# CeeGrid_Anschluss.net
KiCad netlist of a schematic drawn in EAGLE
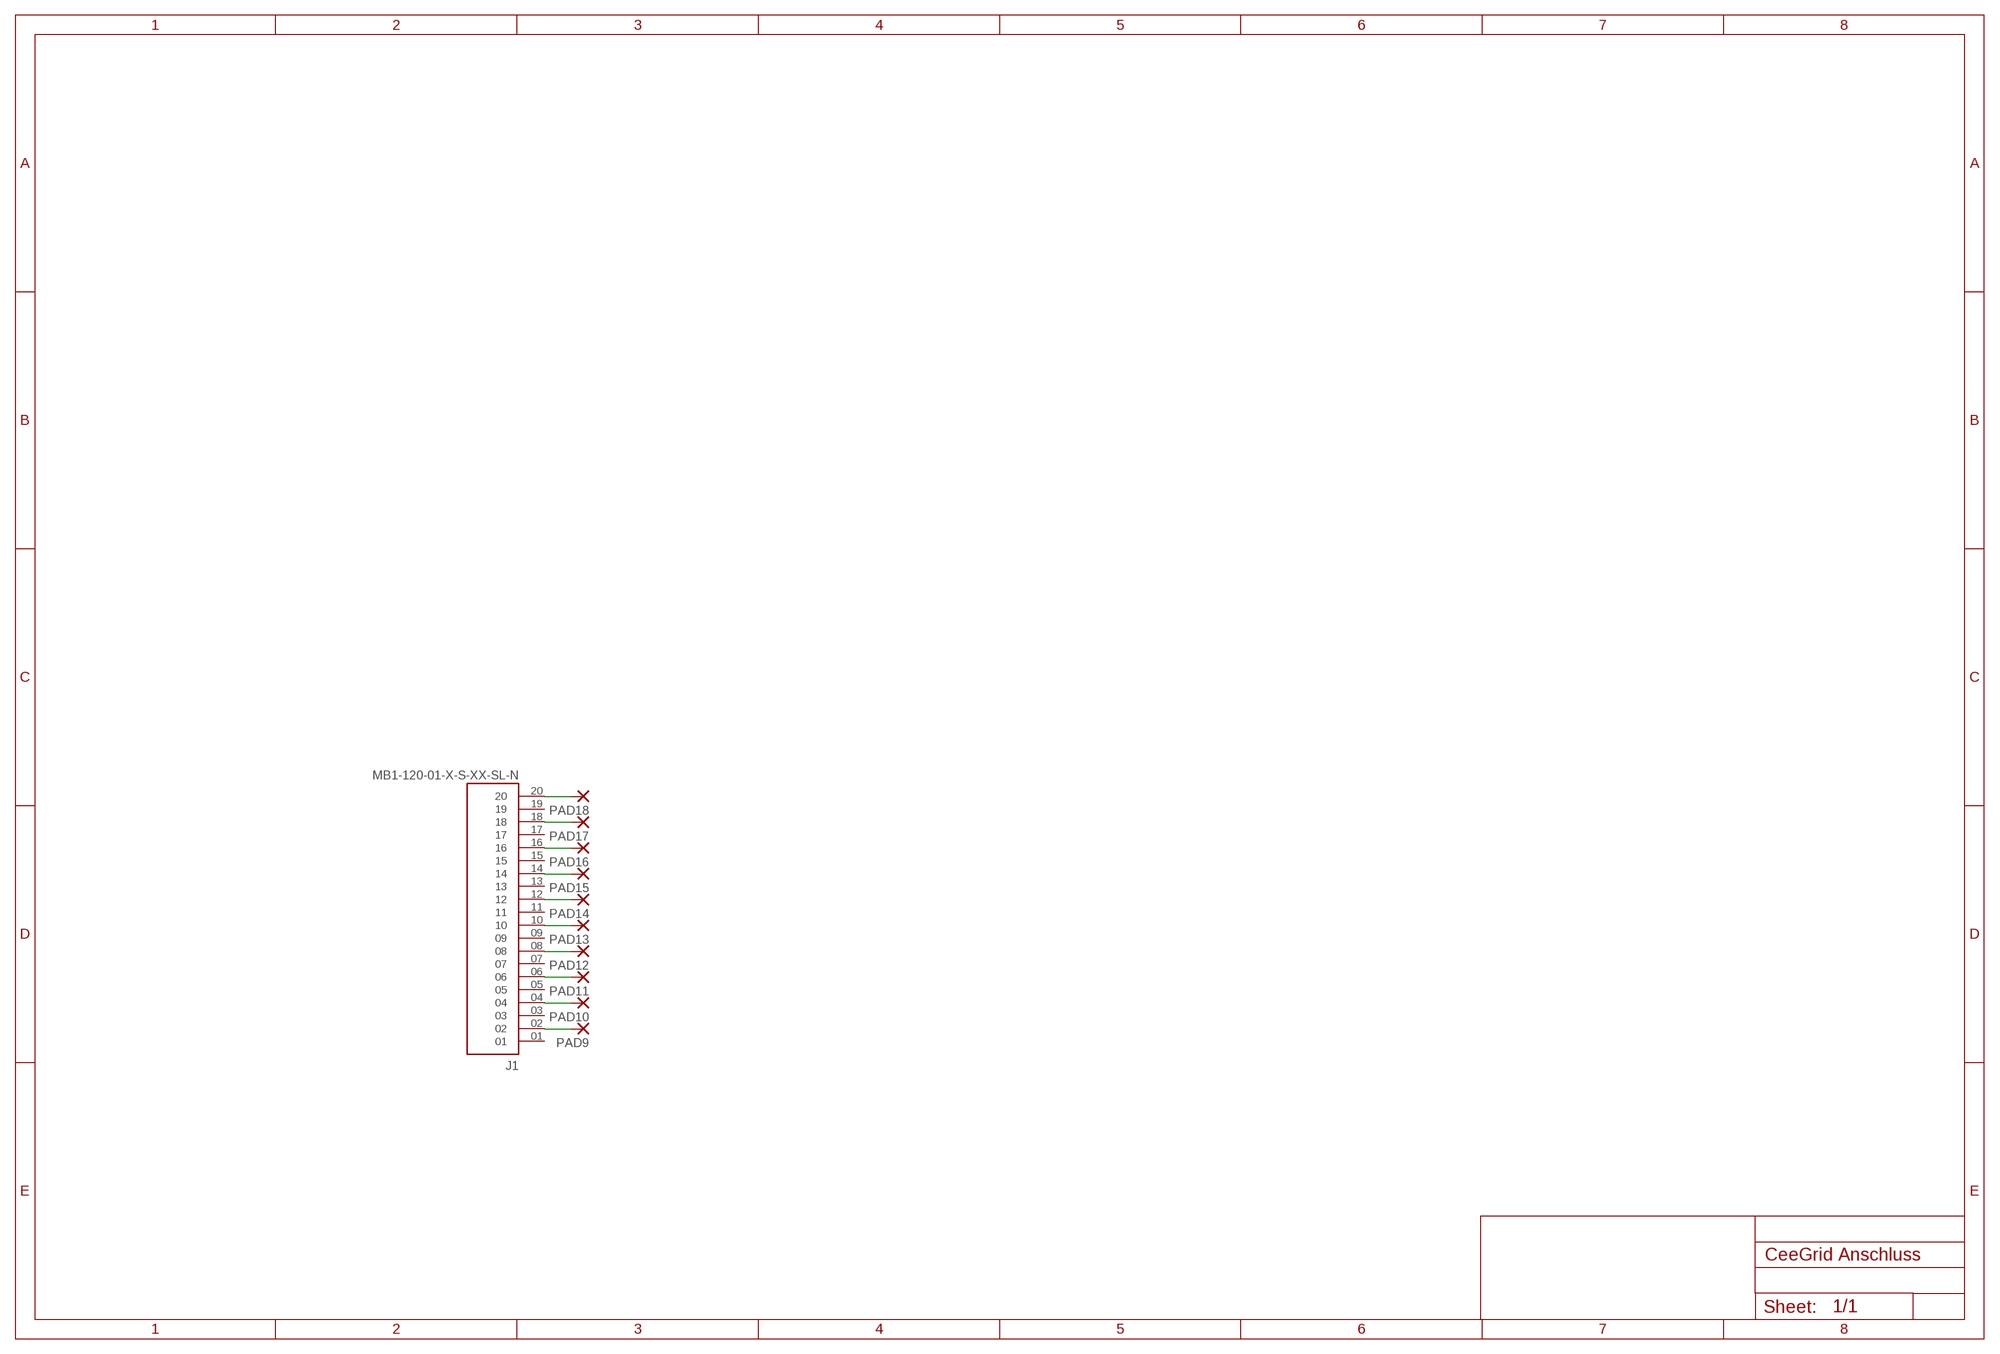
[diagram p0: schematic, sheet 1]

(export (version "E")
  (design (tool "Eeschema 10.0.6"))
  (components
    (comp (ref "J1")
      (value "MB1-120-01-X-S-XX-SL-N")
      (footprint "eagle-import:SAMTEC_MB1-120-01-X-S-XX-SL-N")
      (fields (field (name "MANUFACTURER") "Samtec"))
      (libsource (lib "eagle-import") (part "MB1-120-01-X-S-XX-SL-N"))
    )
    (comp (ref "PAD9")
      (value "SMD2")
      (footprint "eagle-import:SMD1,27-2,54")
      (libsource (lib "eagle-import") (part "SMD2"))
    )
    (comp (ref "PAD10")
      (value "SMD2")
      (footprint "eagle-import:SMD1,27-2,54")
      (libsource (lib "eagle-import") (part "SMD2"))
    )
    (comp (ref "PAD11")
      (value "SMD2")
      (footprint "eagle-import:SMD1,27-2,54")
      (libsource (lib "eagle-import") (part "SMD2"))
    )
    (comp (ref "PAD12")
      (value "SMD2")
      (footprint "eagle-import:SMD1,27-2,54")
      (libsource (lib "eagle-import") (part "SMD2"))
    )
    (comp (ref "PAD13")
      (value "SMD2")
      (footprint "eagle-import:SMD1,27-2,54")
      (libsource (lib "eagle-import") (part "SMD2"))
    )
    (comp (ref "PAD14")
      (value "SMD2")
      (footprint "eagle-import:SMD1,27-2,54")
      (libsource (lib "eagle-import") (part "SMD2"))
    )
    (comp (ref "PAD15")
      (value "SMD2")
      (footprint "eagle-import:SMD1,27-2,54")
      (libsource (lib "eagle-import") (part "SMD2"))
    )
    (comp (ref "PAD16")
      (value "SMD2")
      (footprint "eagle-import:SMD1,27-2,54")
      (libsource (lib "eagle-import") (part "SMD2"))
    )
    (comp (ref "PAD17")
      (value "SMD2")
      (footprint "eagle-import:SMD1,27-2,54")
      (libsource (lib "eagle-import") (part "SMD2"))
    )
    (comp (ref "PAD18")
      (value "SMD2")
      (footprint "eagle-import:SMD1,27-2,54")
      (libsource (lib "eagle-import") (part "SMD2"))
    )
  )
  (nets
    (net (code "1") (name "Net-(PAD9-P)") (class "Default")
      (node (ref "J1") (pin "02") (pinfunction "02_02") (pintype "passive"))
      (node (ref "PAD9") (pin "1") (pinfunction "P_1") (pintype "passive"))
    )
    (net (code "2") (name "Net-(PAD10-P)") (class "Default")
      (node (ref "J1") (pin "04") (pinfunction "04_04") (pintype "passive"))
      (node (ref "PAD10") (pin "1") (pinfunction "P_1") (pintype "passive"))
    )
    (net (code "3") (name "Net-(PAD11-P)") (class "Default")
      (node (ref "J1") (pin "06") (pinfunction "06_06") (pintype "passive"))
      (node (ref "PAD11") (pin "1") (pinfunction "P_1") (pintype "passive"))
    )
    (net (code "4") (name "Net-(PAD12-P)") (class "Default")
      (node (ref "J1") (pin "08") (pinfunction "08_08") (pintype "passive"))
      (node (ref "PAD12") (pin "1") (pinfunction "P_1") (pintype "passive"))
    )
    (net (code "5") (name "Net-(PAD13-P)") (class "Default")
      (node (ref "J1") (pin "10") (pinfunction "10_10") (pintype "passive"))
      (node (ref "PAD13") (pin "1") (pinfunction "P_1") (pintype "passive"))
    )
    (net (code "6") (name "Net-(PAD14-P)") (class "Default")
      (node (ref "J1") (pin "12") (pinfunction "12_12") (pintype "passive"))
      (node (ref "PAD14") (pin "1") (pinfunction "P_1") (pintype "passive"))
    )
    (net (code "7") (name "Net-(PAD15-P)") (class "Default")
      (node (ref "J1") (pin "14") (pinfunction "14_14") (pintype "passive"))
      (node (ref "PAD15") (pin "1") (pinfunction "P_1") (pintype "passive"))
    )
    (net (code "8") (name "Net-(PAD16-P)") (class "Default")
      (node (ref "J1") (pin "16") (pinfunction "16_16") (pintype "passive"))
      (node (ref "PAD16") (pin "1") (pinfunction "P_1") (pintype "passive"))
    )
    (net (code "9") (name "Net-(PAD17-P)") (class "Default")
      (node (ref "J1") (pin "18") (pinfunction "18_18") (pintype "passive"))
      (node (ref "PAD17") (pin "1") (pinfunction "P_1") (pintype "passive"))
    )
    (net (code "10") (name "Net-(PAD18-P)") (class "Default")
      (node (ref "J1") (pin "20") (pinfunction "20_20") (pintype "passive"))
      (node (ref "PAD18") (pin "1") (pinfunction "P_1") (pintype "passive"))
    )
    (net (code "11") (name "unconnected-(J1-Pad01)") (class "Default")
      (node (ref "J1") (pin "01") (pinfunction "01_01") (pintype "passive"))
    )
    (net (code "12") (name "unconnected-(J1-Pad03)") (class "Default")
      (node (ref "J1") (pin "03") (pinfunction "03_03") (pintype "passive"))
    )
    (net (code "13") (name "unconnected-(J1-Pad05)") (class "Default")
      (node (ref "J1") (pin "05") (pinfunction "05_05") (pintype "passive"))
    )
    (net (code "14") (name "unconnected-(J1-Pad07)") (class "Default")
      (node (ref "J1") (pin "07") (pinfunction "07_07") (pintype "passive"))
    )
    (net (code "15") (name "unconnected-(J1-Pad09)") (class "Default")
      (node (ref "J1") (pin "09") (pinfunction "09_09") (pintype "passive"))
    )
    (net (code "16") (name "unconnected-(J1-Pad11)") (class "Default")
      (node (ref "J1") (pin "11") (pinfunction "11_11") (pintype "passive"))
    )
    (net (code "17") (name "unconnected-(J1-Pad13)") (class "Default")
      (node (ref "J1") (pin "13") (pinfunction "13_13") (pintype "passive"))
    )
    (net (code "18") (name "unconnected-(J1-Pad15)") (class "Default")
      (node (ref "J1") (pin "15") (pinfunction "15_15") (pintype "passive"))
    )
    (net (code "19") (name "unconnected-(J1-Pad17)") (class "Default")
      (node (ref "J1") (pin "17") (pinfunction "17_17") (pintype "passive"))
    )
    (net (code "20") (name "unconnected-(J1-Pad19)") (class "Default")
      (node (ref "J1") (pin "19") (pinfunction "19_19") (pintype "passive"))
    )
  )
)
